# Connectors_Wires.net
KiCad netlist of a schematic drawn in Altium Designer
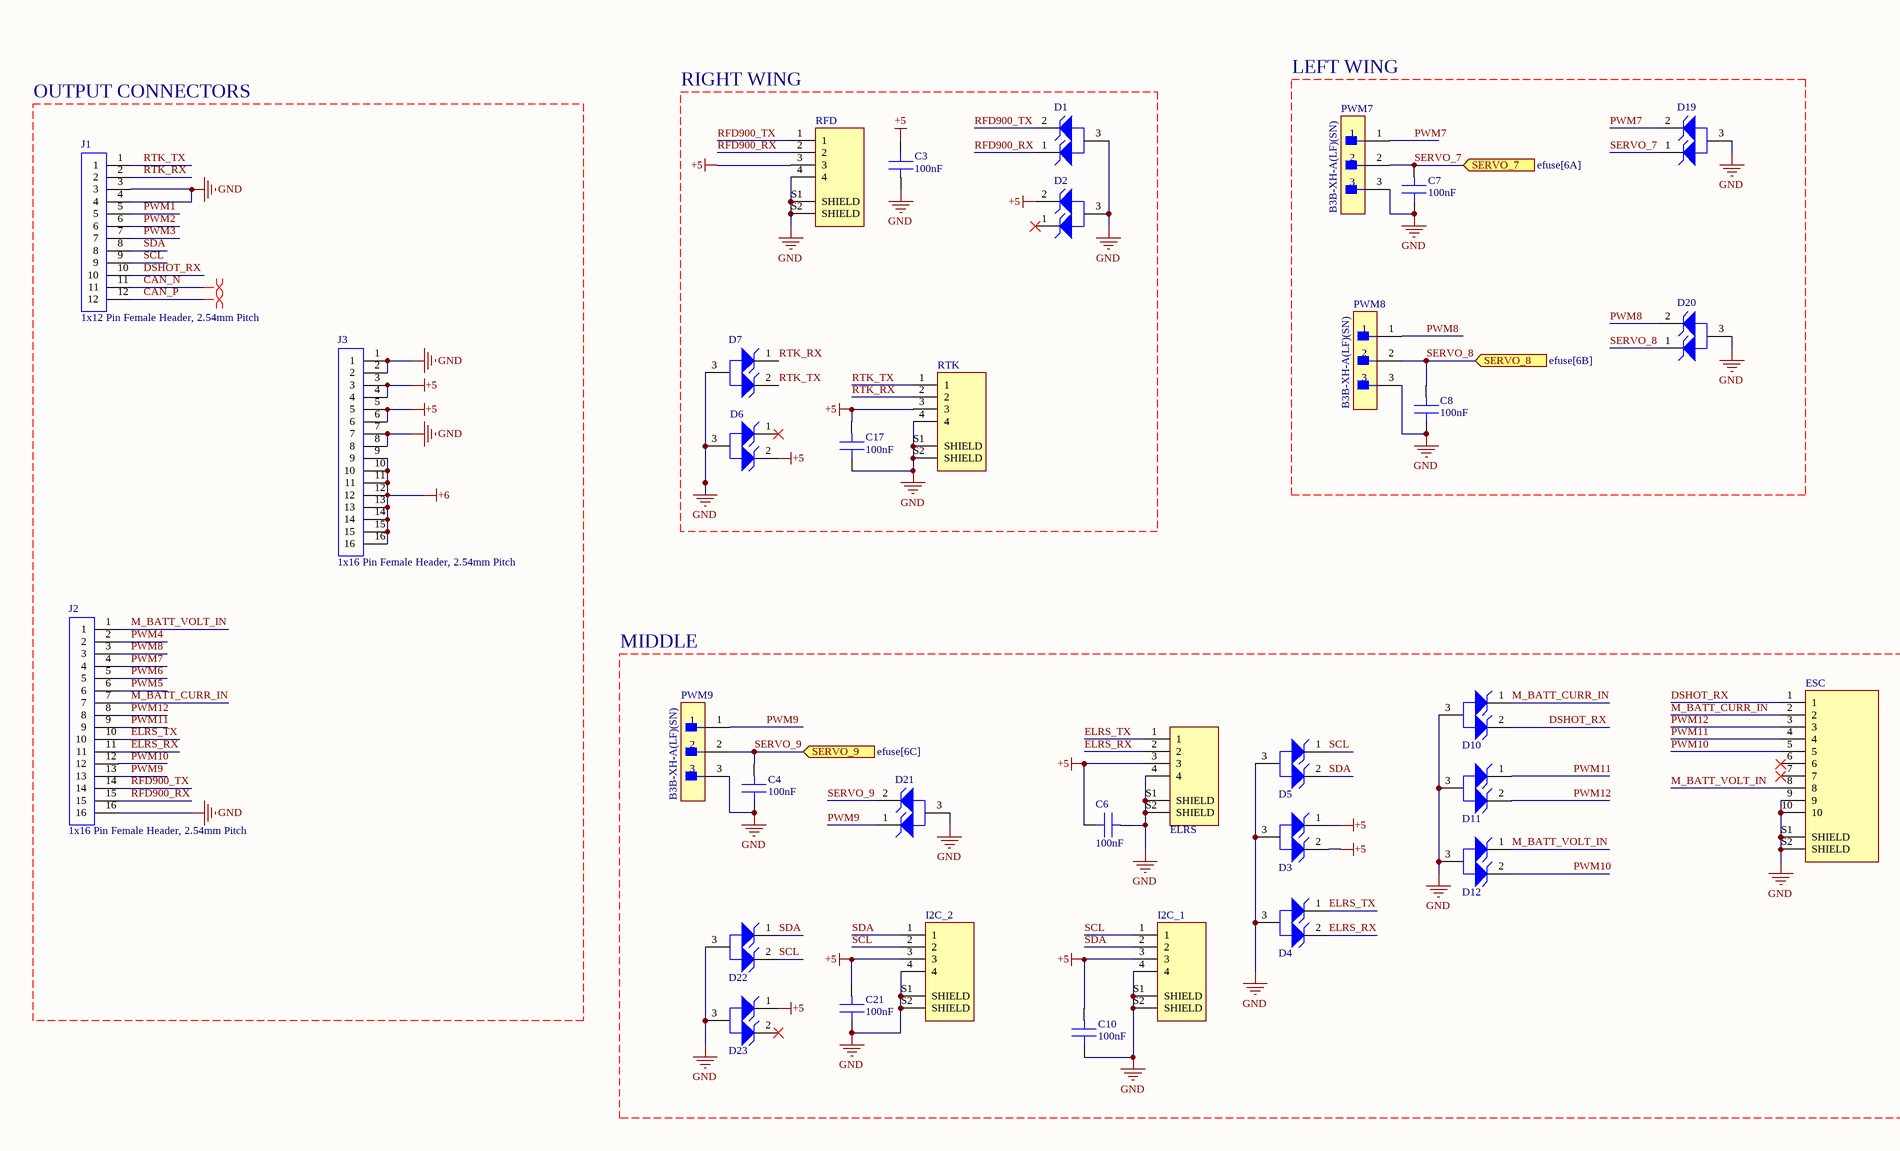
[diagram p0: Connectors_Wires.SchDoc, left]
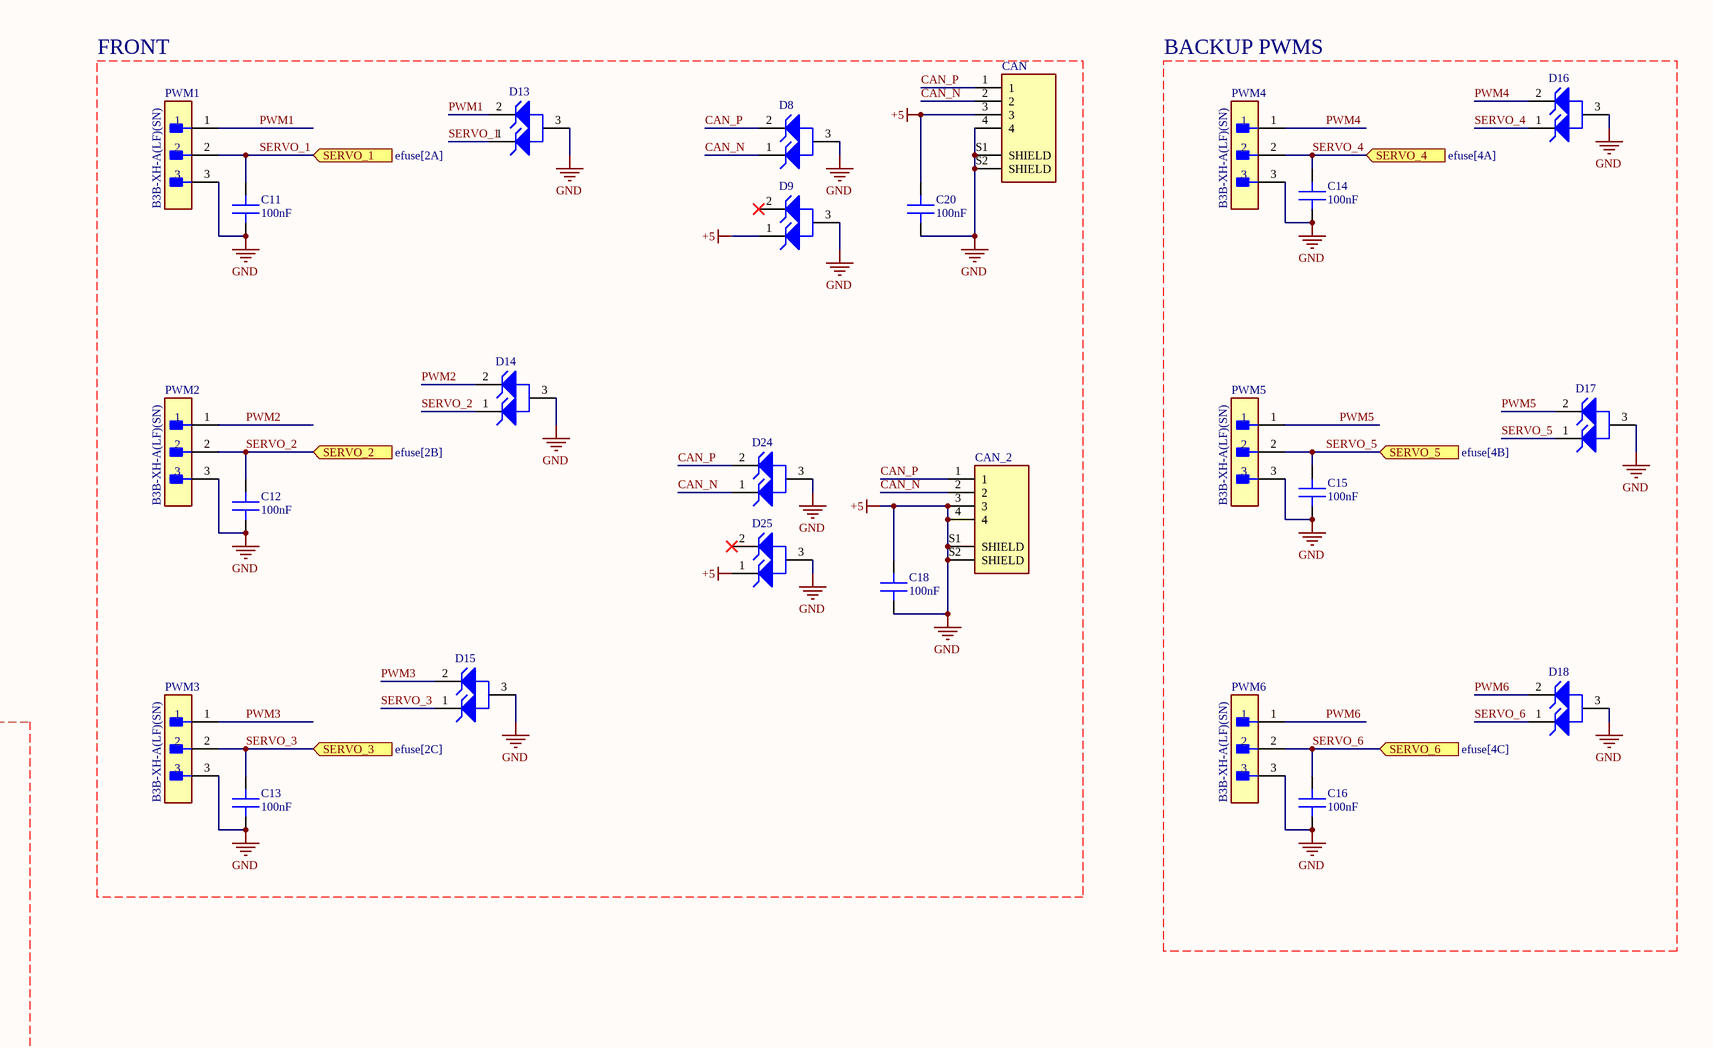
[diagram p1: Connectors_Wires.SchDoc, right]

(export (version "E")
  (design (tool "Eeschema 10.0.6"))
  (components
    (comp (ref "C3")
      (value "100nF")
      (footprint "IPC C C0402 NO SILK")
      (libsource (lib "University of British Columbia") (part "Generic CAP 1210"))
    )
    (comp (ref "C4")
      (value "100nF")
      (footprint "IPC C C0402 NO SILK")
      (libsource (lib "University of British Columbia") (part "Generic CAP 1210"))
    )
    (comp (ref "C6")
      (value "100nF")
      (footprint "IPC C C0402 NO SILK")
      (libsource (lib "University of British Columbia") (part "Generic CAP 1210"))
    )
    (comp (ref "C7")
      (value "100nF")
      (footprint "IPC C C0402 NO SILK")
      (libsource (lib "University of British Columbia") (part "Generic CAP 1210"))
    )
    (comp (ref "C8")
      (value "100nF")
      (footprint "IPC C C0402 NO SILK")
      (libsource (lib "University of British Columbia") (part "Generic CAP 1210"))
    )
    (comp (ref "C10")
      (value "100nF")
      (footprint "IPC C C0402 NO SILK")
      (libsource (lib "University of British Columbia") (part "Generic CAP 1210"))
    )
    (comp (ref "C11")
      (value "100nF")
      (footprint "IPC C C0402 NO SILK")
      (libsource (lib "University of British Columbia") (part "Generic CAP 1210"))
    )
    (comp (ref "C12")
      (value "100nF")
      (footprint "IPC C C0402 NO SILK")
      (libsource (lib "University of British Columbia") (part "Generic CAP 1210"))
    )
    (comp (ref "C13")
      (value "100nF")
      (footprint "IPC C C0402 NO SILK")
      (libsource (lib "University of British Columbia") (part "Generic CAP 1210"))
    )
    (comp (ref "C14")
      (value "100nF")
      (footprint "IPC C C0402 NO SILK")
      (libsource (lib "University of British Columbia") (part "Generic CAP 1210"))
    )
    (comp (ref "C15")
      (value "100nF")
      (footprint "IPC C C0402 NO SILK")
      (libsource (lib "University of British Columbia") (part "Generic CAP 1210"))
    )
    (comp (ref "C16")
      (value "100nF")
      (footprint "IPC C C0402 NO SILK")
      (libsource (lib "University of British Columbia") (part "Generic CAP 1210"))
    )
    (comp (ref "C17")
      (value "100nF")
      (footprint "IPC C C0402 NO SILK")
      (libsource (lib "University of British Columbia") (part "Generic CAP 1210"))
    )
    (comp (ref "C18")
      (value "100nF")
      (footprint "IPC C C0402 NO SILK")
      (libsource (lib "University of British Columbia") (part "Generic CAP 1210"))
    )
    (comp (ref "C20")
      (value "100nF")
      (footprint "IPC C C0402 NO SILK")
      (libsource (lib "University of British Columbia") (part "Generic CAP 1210"))
    )
    (comp (ref "C21")
      (value "100nF")
      (footprint "IPC C C0402 NO SILK")
      (libsource (lib "University of British Columbia") (part "Generic CAP 1210"))
    )
    (comp (ref "CAN")
      (value "BM04B-GHS-TBT(LF)(SN)(N)")
      (footprint "JST_BM04B-GHS-TBT(LF)(SN)(N)")
      (description "Conn Shrouded Header HDR 4 POS 1.25mm Solder ST Top Entry SMD T/R")
      (fields (field (name "MF") "JST") (field (name "MP") "BM04B-GHS-TBT (LF)(SN)(N)"))
      (libsource (lib "University of British Columbia") (part "BM04B-GHS-TBT(LF)(SN)(N)"))
    )
    (comp (ref "CAN_2")
      (value "BM04B-GHS-TBT(LF)(SN)(N)")
      (footprint "JST_BM04B-GHS-TBT(LF)(SN)(N)")
      (description "Conn Shrouded Header HDR 4 POS 1.25mm Solder ST Top Entry SMD T/R")
      (fields (field (name "MF") "JST") (field (name "MP") "BM04B-GHS-TBT (LF)(SN)(N)"))
      (libsource (lib "University of British Columbia") (part "BM04B-GHS-TBT(LF)(SN)(N)"))
    )
    (comp (ref "D1")
      (value "MMBZ9V1ALT1G")
      (footprint "ONSC-SOT-23-3-318-08_V")
      (fields (field (name "MANUFACTURER") "On Semiconductor"))
      (libsource (lib "Altium Content Vault") (part "ONSC-K1K2A3-3"))
    )
    (comp (ref "D2")
      (value "MMBZ9V1ALT1G")
      (footprint "ONSC-SOT-23-3-318-08_V")
      (fields (field (name "MANUFACTURER") "On Semiconductor"))
      (libsource (lib "Altium Content Vault") (part "ONSC-K1K2A3-3"))
    )
    (comp (ref "D3")
      (value "MMBZ9V1ALT1G")
      (footprint "ONSC-SOT-23-3-318-08_V")
      (fields (field (name "MANUFACTURER") "On Semiconductor"))
      (libsource (lib "Altium Content Vault") (part "ONSC-K1K2A3-3"))
    )
    (comp (ref "D4")
      (value "MMBZ9V1ALT1G")
      (footprint "ONSC-SOT-23-3-318-08_V")
      (fields (field (name "MANUFACTURER") "On Semiconductor"))
      (libsource (lib "Altium Content Vault") (part "ONSC-K1K2A3-3"))
    )
    (comp (ref "D5")
      (value "MMBZ9V1ALT1G")
      (footprint "ONSC-SOT-23-3-318-08_V")
      (fields (field (name "MANUFACTURER") "On Semiconductor"))
      (libsource (lib "Altium Content Vault") (part "ONSC-K1K2A3-3"))
    )
    (comp (ref "D6")
      (value "MMBZ9V1ALT1G")
      (footprint "ONSC-SOT-23-3-318-08_V")
      (fields (field (name "MANUFACTURER") "On Semiconductor"))
      (libsource (lib "Altium Content Vault") (part "ONSC-K1K2A3-3"))
    )
    (comp (ref "D7")
      (value "MMBZ9V1ALT1G")
      (footprint "ONSC-SOT-23-3-318-08_V")
      (fields (field (name "MANUFACTURER") "On Semiconductor"))
      (libsource (lib "Altium Content Vault") (part "ONSC-K1K2A3-3"))
    )
    (comp (ref "D8")
      (value "MMBZ9V1ALT1G")
      (footprint "ONSC-SOT-23-3-318-08_V")
      (fields (field (name "MANUFACTURER") "On Semiconductor"))
      (libsource (lib "Altium Content Vault") (part "ONSC-K1K2A3-3"))
    )
    (comp (ref "D9")
      (value "MMBZ9V1ALT1G")
      (footprint "ONSC-SOT-23-3-318-08_V")
      (fields (field (name "MANUFACTURER") "On Semiconductor"))
      (libsource (lib "Altium Content Vault") (part "ONSC-K1K2A3-3"))
    )
    (comp (ref "D10")
      (value "MMBZ9V1ALT1G")
      (footprint "ONSC-SOT-23-3-318-08_V")
      (fields (field (name "MANUFACTURER") "On Semiconductor"))
      (libsource (lib "Altium Content Vault") (part "ONSC-K1K2A3-3"))
    )
    (comp (ref "D11")
      (value "MMBZ9V1ALT1G")
      (footprint "ONSC-SOT-23-3-318-08_V")
      (fields (field (name "MANUFACTURER") "On Semiconductor"))
      (libsource (lib "Altium Content Vault") (part "ONSC-K1K2A3-3"))
    )
    (comp (ref "D12")
      (value "MMBZ9V1ALT1G")
      (footprint "ONSC-SOT-23-3-318-08_V")
      (fields (field (name "MANUFACTURER") "On Semiconductor"))
      (libsource (lib "Altium Content Vault") (part "ONSC-K1K2A3-3"))
    )
    (comp (ref "D13")
      (value "MMBZ9V1ALT1G")
      (footprint "ONSC-SOT-23-3-318-08_V")
      (fields (field (name "MANUFACTURER") "On Semiconductor"))
      (libsource (lib "Altium Content Vault") (part "ONSC-K1K2A3-3"))
    )
    (comp (ref "D14")
      (value "MMBZ9V1ALT1G")
      (footprint "ONSC-SOT-23-3-318-08_V")
      (fields (field (name "MANUFACTURER") "On Semiconductor"))
      (libsource (lib "Altium Content Vault") (part "ONSC-K1K2A3-3"))
    )
    (comp (ref "D15")
      (value "MMBZ9V1ALT1G")
      (footprint "ONSC-SOT-23-3-318-08_V")
      (fields (field (name "MANUFACTURER") "On Semiconductor"))
      (libsource (lib "Altium Content Vault") (part "ONSC-K1K2A3-3"))
    )
    (comp (ref "D16")
      (value "MMBZ9V1ALT1G")
      (footprint "ONSC-SOT-23-3-318-08_V")
      (fields (field (name "MANUFACTURER") "On Semiconductor"))
      (libsource (lib "Altium Content Vault") (part "ONSC-K1K2A3-3"))
    )
    (comp (ref "D17")
      (value "MMBZ9V1ALT1G")
      (footprint "ONSC-SOT-23-3-318-08_V")
      (fields (field (name "MANUFACTURER") "On Semiconductor"))
      (libsource (lib "Altium Content Vault") (part "ONSC-K1K2A3-3"))
    )
    (comp (ref "D18")
      (value "MMBZ9V1ALT1G")
      (footprint "ONSC-SOT-23-3-318-08_V")
      (fields (field (name "MANUFACTURER") "On Semiconductor"))
      (libsource (lib "Altium Content Vault") (part "ONSC-K1K2A3-3"))
    )
    (comp (ref "D19")
      (value "MMBZ9V1ALT1G")
      (footprint "ONSC-SOT-23-3-318-08_V")
      (fields (field (name "MANUFACTURER") "On Semiconductor"))
      (libsource (lib "Altium Content Vault") (part "ONSC-K1K2A3-3"))
    )
    (comp (ref "D20")
      (value "MMBZ9V1ALT1G")
      (footprint "ONSC-SOT-23-3-318-08_V")
      (fields (field (name "MANUFACTURER") "On Semiconductor"))
      (libsource (lib "Altium Content Vault") (part "ONSC-K1K2A3-3"))
    )
    (comp (ref "D21")
      (value "MMBZ9V1ALT1G")
      (footprint "ONSC-SOT-23-3-318-08_V")
      (fields (field (name "MANUFACTURER") "On Semiconductor"))
      (libsource (lib "Altium Content Vault") (part "ONSC-K1K2A3-3"))
    )
    (comp (ref "D22")
      (value "MMBZ9V1ALT1G")
      (footprint "ONSC-SOT-23-3-318-08_V")
      (fields (field (name "MANUFACTURER") "On Semiconductor"))
      (libsource (lib "Altium Content Vault") (part "ONSC-K1K2A3-3"))
    )
    (comp (ref "D23")
      (value "MMBZ9V1ALT1G")
      (footprint "ONSC-SOT-23-3-318-08_V")
      (fields (field (name "MANUFACTURER") "On Semiconductor"))
      (libsource (lib "Altium Content Vault") (part "ONSC-K1K2A3-3"))
    )
    (comp (ref "D24")
      (value "MMBZ9V1ALT1G")
      (footprint "ONSC-SOT-23-3-318-08_V")
      (fields (field (name "MANUFACTURER") "On Semiconductor"))
      (libsource (lib "Altium Content Vault") (part "ONSC-K1K2A3-3"))
    )
    (comp (ref "D25")
      (value "MMBZ9V1ALT1G")
      (footprint "ONSC-SOT-23-3-318-08_V")
      (fields (field (name "MANUFACTURER") "On Semiconductor"))
      (libsource (lib "Altium Content Vault") (part "ONSC-K1K2A3-3"))
    )
    (comp (ref "ELRS")
      (value "BM04B-GHS-TBT(LF)(SN)(N)")
      (footprint "JST_BM04B-GHS-TBT(LF)(SN)(N)")
      (description "Conn Shrouded Header HDR 4 POS 1.25mm Solder ST Top Entry SMD T/R")
      (fields (field (name "MF") "JST") (field (name "MP") "BM04B-GHS-TBT (LF)(SN)(N)"))
      (libsource (lib "University of British Columbia") (part "BM04B-GHS-TBT(LF)(SN)(N)"))
    )
    (comp (ref "ESC")
      (value "BM10B-GHS-TBT(LF)(SN)(N)")
      (footprint "JST_BM10B-GHS-TBT(LF)(SN)(N)")
      (description "Connector Header Surface Mount 10 position 0.049 (1.25mm)")
      (fields (field (name "MF") "JST Sales"))
      (libsource (lib "University of British Columbia") (part "BM10B-GHS-TBT(LF)(SN)(N)"))
    )
    (comp (ref "I2C_1")
      (value "BM04B-GHS-TBT(LF)(SN)(N)")
      (footprint "JST_BM04B-GHS-TBT(LF)(SN)(N)")
      (description "Conn Shrouded Header HDR 4 POS 1.25mm Solder ST Top Entry SMD T/R")
      (fields (field (name "MF") "JST") (field (name "MP") "BM04B-GHS-TBT (LF)(SN)(N)"))
      (libsource (lib "University of British Columbia") (part "BM04B-GHS-TBT(LF)(SN)(N)"))
    )
    (comp (ref "I2C_2")
      (value "BM04B-GHS-TBT(LF)(SN)(N)")
      (footprint "JST_BM04B-GHS-TBT(LF)(SN)(N)")
      (description "Conn Shrouded Header HDR 4 POS 1.25mm Solder ST Top Entry SMD T/R")
      (fields (field (name "MF") "JST") (field (name "MP") "BM04B-GHS-TBT (LF)(SN)(N)"))
      (libsource (lib "University of British Columbia") (part "BM04B-GHS-TBT(LF)(SN)(N)"))
    )
    (comp (ref "J1")
      (value "1x12 Pin Female Header, 2.54mm Pitch")
      (footprint "1x12 Pin Female Header, 2.54mm Pitch-Footprint-1")
      (libsource (lib "University of British Columbia") (part "1x12 Pin Female Header, 2.54mm Pitch-Symbol-1"))
    )
    (comp (ref "J2")
      (value "1x16 Pin Female Header, 2.54mm Pitch")
      (footprint "New footprint 1")
      (libsource (lib "University of British Columbia") (part "New symbol 1"))
    )
    (comp (ref "J3")
      (value "1x16 Pin Female Header, 2.54mm Pitch")
      (footprint "New footprint 1")
      (libsource (lib "University of British Columbia") (part "New symbol 1"))
    )
    (comp (ref "PWM1")
      (value "B3B-XH-A(LF)(SN)")
      (footprint "FP-B3B-XH-A_LF_SN-MFG")
      (description "CONN HEADER VERT 3POS 2.5MM")
      (libsource (lib "Altium Content Vault") (part "0d3f023dd272f625e17a2be33dea85f"))
    )
    (comp (ref "PWM2")
      (value "B3B-XH-A(LF)(SN)")
      (footprint "FP-B3B-XH-A_LF_SN-MFG")
      (description "CONN HEADER VERT 3POS 2.5MM")
      (libsource (lib "Altium Content Vault") (part "0d3f023dd272f625e17a2be33dea85f"))
    )
    (comp (ref "PWM3")
      (value "B3B-XH-A(LF)(SN)")
      (footprint "FP-B3B-XH-A_LF_SN-MFG")
      (description "CONN HEADER VERT 3POS 2.5MM")
      (libsource (lib "Altium Content Vault") (part "0d3f023dd272f625e17a2be33dea85f"))
    )
    (comp (ref "PWM4")
      (value "B3B-XH-A(LF)(SN)")
      (footprint "FP-B3B-XH-A_LF_SN-MFG")
      (description "CONN HEADER VERT 3POS 2.5MM")
      (libsource (lib "Altium Content Vault") (part "0d3f023dd272f625e17a2be33dea85f"))
    )
    (comp (ref "PWM5")
      (value "B3B-XH-A(LF)(SN)")
      (footprint "FP-B3B-XH-A_LF_SN-MFG")
      (description "CONN HEADER VERT 3POS 2.5MM")
      (libsource (lib "Altium Content Vault") (part "0d3f023dd272f625e17a2be33dea85f"))
    )
    (comp (ref "PWM6")
      (value "B3B-XH-A(LF)(SN)")
      (footprint "FP-B3B-XH-A_LF_SN-MFG")
      (description "CONN HEADER VERT 3POS 2.5MM")
      (libsource (lib "Altium Content Vault") (part "0d3f023dd272f625e17a2be33dea85f"))
    )
    (comp (ref "PWM7")
      (value "B3B-XH-A(LF)(SN)")
      (footprint "FP-B3B-XH-A_LF_SN-MFG")
      (description "CONN HEADER VERT 3POS 2.5MM")
      (libsource (lib "Altium Content Vault") (part "0d3f023dd272f625e17a2be33dea85f"))
    )
    (comp (ref "PWM8")
      (value "B3B-XH-A(LF)(SN)")
      (footprint "FP-B3B-XH-A_LF_SN-MFG")
      (description "CONN HEADER VERT 3POS 2.5MM")
      (libsource (lib "Altium Content Vault") (part "0d3f023dd272f625e17a2be33dea85f"))
    )
    (comp (ref "PWM9")
      (value "B3B-XH-A(LF)(SN)")
      (footprint "FP-B3B-XH-A_LF_SN-MFG")
      (description "CONN HEADER VERT 3POS 2.5MM")
      (libsource (lib "Altium Content Vault") (part "0d3f023dd272f625e17a2be33dea85f"))
    )
    (comp (ref "RFD")
      (value "BM04B-GHS-TBT(LF)(SN)(N)")
      (footprint "JST_BM04B-GHS-TBT(LF)(SN)(N)")
      (description "Conn Shrouded Header HDR 4 POS 1.25mm Solder ST Top Entry SMD T/R")
      (fields (field (name "MF") "JST") (field (name "MP") "BM04B-GHS-TBT (LF)(SN)(N)"))
      (libsource (lib "University of British Columbia") (part "BM04B-GHS-TBT(LF)(SN)(N)"))
    )
    (comp (ref "RTK")
      (value "BM04B-GHS-TBT(LF)(SN)(N)")
      (footprint "JST_BM04B-GHS-TBT(LF)(SN)(N)")
      (description "Conn Shrouded Header HDR 4 POS 1.25mm Solder ST Top Entry SMD T/R")
      (fields (field (name "MF") "JST") (field (name "MP") "BM04B-GHS-TBT (LF)(SN)(N)"))
      (libsource (lib "University of British Columbia") (part "BM04B-GHS-TBT(LF)(SN)(N)"))
    )
  )
  (nets
    (net (code "1") (name "+5") (class "Default")
      (node (ref "C10") (pin "1") (pinfunction "1_1") (pintype "passive"))
      (node (ref "C10") (pin "2") (pinfunction "2_2") (pintype "passive"))
      (node (ref "C11") (pin "2") (pinfunction "2_2") (pintype "passive"))
      (node (ref "C12") (pin "2") (pinfunction "2_2") (pintype "passive"))
      (node (ref "C13") (pin "2") (pinfunction "2_2") (pintype "passive"))
      (node (ref "C14") (pin "2") (pinfunction "2_2") (pintype "passive"))
      (node (ref "C15") (pin "2") (pinfunction "2_2") (pintype "passive"))
      (node (ref "C16") (pin "2") (pinfunction "2_2") (pintype "passive"))
      (node (ref "C17") (pin "1") (pinfunction "1_1") (pintype "passive"))
      (node (ref "C17") (pin "2") (pinfunction "2_2") (pintype "passive"))
      (node (ref "C18") (pin "1") (pinfunction "1_1") (pintype "passive"))
      (node (ref "C18") (pin "2") (pinfunction "2_2") (pintype "passive"))
      (node (ref "C20") (pin "1") (pinfunction "1_1") (pintype "passive"))
      (node (ref "C20") (pin "2") (pinfunction "2_2") (pintype "passive"))
      (node (ref "C21") (pin "1") (pinfunction "1_1") (pintype "passive"))
      (node (ref "C21") (pin "2") (pinfunction "2_2") (pintype "passive"))
      (node (ref "C3") (pin "1") (pinfunction "1_1") (pintype "passive"))
      (node (ref "C3") (pin "2") (pinfunction "2_2") (pintype "passive"))
      (node (ref "C4") (pin "2") (pinfunction "2_2") (pintype "passive"))
      (node (ref "C6") (pin "1") (pinfunction "1_1") (pintype "passive"))
      (node (ref "C6") (pin "2") (pinfunction "2_2") (pintype "passive"))
      (node (ref "C7") (pin "2") (pinfunction "2_2") (pintype "passive"))
      (node (ref "C8") (pin "2") (pinfunction "2_2") (pintype "passive"))
      (node (ref "CAN") (pin "3") (pinfunction "3_3") (pintype "passive"))
      (node (ref "CAN") (pin "4") (pinfunction "4_4") (pintype "passive"))
      (node (ref "CAN") (pin "S1") (pinfunction "SHIELD_S1") (pintype "passive"))
      (node (ref "CAN") (pin "S2") (pinfunction "SHIELD_S2") (pintype "passive"))
      (node (ref "CAN_2") (pin "3") (pinfunction "3_3") (pintype "passive"))
      (node (ref "CAN_2") (pin "4") (pinfunction "4_4") (pintype "passive"))
      (node (ref "CAN_2") (pin "S1") (pinfunction "SHIELD_S1") (pintype "passive"))
      (node (ref "CAN_2") (pin "S2") (pinfunction "SHIELD_S2") (pintype "passive"))
      (node (ref "D1") (pin "3") (pinfunction "A_3") (pintype "passive"))
      (node (ref "D10") (pin "3") (pinfunction "A_3") (pintype "passive"))
      (node (ref "D11") (pin "3") (pinfunction "A_3") (pintype "passive"))
      (node (ref "D12") (pin "3") (pinfunction "A_3") (pintype "passive"))
      (node (ref "D13") (pin "3") (pinfunction "A_3") (pintype "passive"))
      (node (ref "D14") (pin "3") (pinfunction "A_3") (pintype "passive"))
      (node (ref "D15") (pin "3") (pinfunction "A_3") (pintype "passive"))
      (node (ref "D16") (pin "3") (pinfunction "A_3") (pintype "passive"))
      (node (ref "D17") (pin "3") (pinfunction "A_3") (pintype "passive"))
      (node (ref "D18") (pin "3") (pinfunction "A_3") (pintype "passive"))
      (node (ref "D19") (pin "3") (pinfunction "A_3") (pintype "passive"))
      (node (ref "D2") (pin "2") (pinfunction "K2_2") (pintype "passive"))
      (node (ref "D2") (pin "3") (pinfunction "A_3") (pintype "passive"))
      (node (ref "D20") (pin "3") (pinfunction "A_3") (pintype "passive"))
      (node (ref "D21") (pin "3") (pinfunction "A_3") (pintype "passive"))
      (node (ref "D22") (pin "3") (pinfunction "A_3") (pintype "passive"))
      (node (ref "D23") (pin "1") (pinfunction "K1_1") (pintype "passive"))
      (node (ref "D23") (pin "3") (pinfunction "A_3") (pintype "passive"))
      (node (ref "D24") (pin "3") (pinfunction "A_3") (pintype "passive"))
      (node (ref "D25") (pin "1") (pinfunction "K1_1") (pintype "passive"))
      (node (ref "D25") (pin "3") (pinfunction "A_3") (pintype "passive"))
      (node (ref "D3") (pin "1") (pinfunction "K1_1") (pintype "passive"))
      (node (ref "D3") (pin "2") (pinfunction "K2_2") (pintype "passive"))
      (node (ref "D3") (pin "3") (pinfunction "A_3") (pintype "passive"))
      (node (ref "D4") (pin "3") (pinfunction "A_3") (pintype "passive"))
      (node (ref "D5") (pin "3") (pinfunction "A_3") (pintype "passive"))
      (node (ref "D6") (pin "2") (pinfunction "K2_2") (pintype "passive"))
      (node (ref "D6") (pin "3") (pinfunction "A_3") (pintype "passive"))
      (node (ref "D7") (pin "3") (pinfunction "A_3") (pintype "passive"))
      (node (ref "D8") (pin "3") (pinfunction "A_3") (pintype "passive"))
      (node (ref "D9") (pin "1") (pinfunction "K1_1") (pintype "passive"))
      (node (ref "D9") (pin "3") (pinfunction "A_3") (pintype "passive"))
      (node (ref "ELRS") (pin "3") (pinfunction "3_3") (pintype "passive"))
      (node (ref "ELRS") (pin "4") (pinfunction "4_4") (pintype "passive"))
      (node (ref "ELRS") (pin "S1") (pinfunction "SHIELD_S1") (pintype "passive"))
      (node (ref "ELRS") (pin "S2") (pinfunction "SHIELD_S2") (pintype "passive"))
      (node (ref "ESC") (pin "10") (pinfunction "10_10") (pintype "passive"))
      (node (ref "ESC") (pin "9") (pinfunction "9_9") (pintype "passive"))
      (node (ref "ESC") (pin "S1") (pinfunction "SHIELD_S1") (pintype "passive"))
      (node (ref "ESC") (pin "S2") (pinfunction "SHIELD_S2") (pintype "passive"))
      (node (ref "I2C_1") (pin "3") (pinfunction "3_3") (pintype "passive"))
      (node (ref "I2C_1") (pin "4") (pinfunction "4_4") (pintype "passive"))
      (node (ref "I2C_1") (pin "S1") (pinfunction "SHIELD_S1") (pintype "passive"))
      (node (ref "I2C_1") (pin "S2") (pinfunction "SHIELD_S2") (pintype "passive"))
      (node (ref "I2C_2") (pin "3") (pinfunction "3_3") (pintype "passive"))
      (node (ref "I2C_2") (pin "4") (pinfunction "4_4") (pintype "passive"))
      (node (ref "I2C_2") (pin "S1") (pinfunction "SHIELD_S1") (pintype "passive"))
      (node (ref "I2C_2") (pin "S2") (pinfunction "SHIELD_S2") (pintype "passive"))
      (node (ref "J1") (pin "3") (pinfunction "3_3") (pintype "passive"))
      (node (ref "J1") (pin "4") (pinfunction "4_4") (pintype "passive"))
      (node (ref "J2") (pin "16") (pinfunction "16_16") (pintype "passive"))
      (node (ref "J3") (pin "1") (pinfunction "1_1") (pintype "passive"))
      (node (ref "J3") (pin "2") (pinfunction "2_2") (pintype "passive"))
      (node (ref "J3") (pin "3") (pinfunction "3_3") (pintype "passive"))
      (node (ref "J3") (pin "4") (pinfunction "4_4") (pintype "passive"))
      (node (ref "J3") (pin "5") (pinfunction "5_5") (pintype "passive"))
      (node (ref "J3") (pin "6") (pinfunction "6_6") (pintype "passive"))
      (node (ref "J3") (pin "7") (pinfunction "7_7") (pintype "passive"))
      (node (ref "J3") (pin "8") (pinfunction "8_8") (pintype "passive"))
      (node (ref "PWM1") (pin "3") (pinfunction "3_3") (pintype "passive"))
      (node (ref "PWM2") (pin "3") (pinfunction "3_3") (pintype "passive"))
      (node (ref "PWM3") (pin "3") (pinfunction "3_3") (pintype "passive"))
      (node (ref "PWM4") (pin "3") (pinfunction "3_3") (pintype "passive"))
      (node (ref "PWM5") (pin "3") (pinfunction "3_3") (pintype "passive"))
      (node (ref "PWM6") (pin "3") (pinfunction "3_3") (pintype "passive"))
      (node (ref "PWM7") (pin "3") (pinfunction "3_3") (pintype "passive"))
      (node (ref "PWM8") (pin "3") (pinfunction "3_3") (pintype "passive"))
      (node (ref "PWM9") (pin "3") (pinfunction "3_3") (pintype "passive"))
      (node (ref "RFD") (pin "3") (pinfunction "3_3") (pintype "passive"))
      (node (ref "RFD") (pin "4") (pinfunction "4_4") (pintype "passive"))
      (node (ref "RFD") (pin "S1") (pinfunction "SHIELD_S1") (pintype "passive"))
      (node (ref "RFD") (pin "S2") (pinfunction "SHIELD_S2") (pintype "passive"))
      (node (ref "RTK") (pin "3") (pinfunction "3_3") (pintype "passive"))
      (node (ref "RTK") (pin "4") (pinfunction "4_4") (pintype "passive"))
      (node (ref "RTK") (pin "S1") (pinfunction "SHIELD_S1") (pintype "passive"))
      (node (ref "RTK") (pin "S2") (pinfunction "SHIELD_S2") (pintype "passive"))
    )
    (net (code "2") (name "+6") (class "Default")
      (node (ref "J3") (pin "10") (pinfunction "10_10") (pintype "passive"))
      (node (ref "J3") (pin "11") (pinfunction "11_11") (pintype "passive"))
      (node (ref "J3") (pin "12") (pinfunction "12_12") (pintype "passive"))
      (node (ref "J3") (pin "13") (pinfunction "13_13") (pintype "passive"))
      (node (ref "J3") (pin "14") (pinfunction "14_14") (pintype "passive"))
      (node (ref "J3") (pin "15") (pinfunction "15_15") (pintype "passive"))
      (node (ref "J3") (pin "16") (pinfunction "16_16") (pintype "passive"))
      (node (ref "J3") (pin "9") (pinfunction "9_9") (pintype "passive"))
    )
    (net (code "3") (name "/CAN_N") (class "Default")
      (node (ref "CAN") (pin "2") (pinfunction "2_2") (pintype "passive"))
      (node (ref "CAN_2") (pin "2") (pinfunction "2_2") (pintype "passive"))
      (node (ref "D24") (pin "1") (pinfunction "K1_1") (pintype "passive"))
      (node (ref "D8") (pin "1") (pinfunction "K1_1") (pintype "passive"))
      (node (ref "J1") (pin "11") (pinfunction "11_11") (pintype "passive"))
    )
    (net (code "4") (name "/CAN_P") (class "Default")
      (node (ref "CAN") (pin "1") (pinfunction "1_1") (pintype "passive"))
      (node (ref "CAN_2") (pin "1") (pinfunction "1_1") (pintype "passive"))
      (node (ref "D24") (pin "2") (pinfunction "K2_2") (pintype "passive"))
      (node (ref "D8") (pin "2") (pinfunction "K2_2") (pintype "passive"))
      (node (ref "J1") (pin "12") (pinfunction "12_12") (pintype "passive"))
    )
    (net (code "5") (name "/DSHOT_RX") (class "Default")
      (node (ref "D10") (pin "2") (pinfunction "K2_2") (pintype "passive"))
      (node (ref "ESC") (pin "1") (pinfunction "1_1") (pintype "passive"))
      (node (ref "J1") (pin "10") (pinfunction "10_10") (pintype "passive"))
    )
    (net (code "6") (name "/ELRS_RX") (class "Default")
      (node (ref "D4") (pin "2") (pinfunction "K2_2") (pintype "passive"))
      (node (ref "ELRS") (pin "2") (pinfunction "2_2") (pintype "passive"))
      (node (ref "J2") (pin "11") (pinfunction "11_11") (pintype "passive"))
    )
    (net (code "7") (name "/ELRS_TX") (class "Default")
      (node (ref "D4") (pin "1") (pinfunction "K1_1") (pintype "passive"))
      (node (ref "ELRS") (pin "1") (pinfunction "1_1") (pintype "passive"))
      (node (ref "J2") (pin "10") (pinfunction "10_10") (pintype "passive"))
    )
    (net (code "8") (name "/M_BATT_CURR_IN") (class "Default")
      (node (ref "D10") (pin "1") (pinfunction "K1_1") (pintype "passive"))
      (node (ref "ESC") (pin "2") (pinfunction "2_2") (pintype "passive"))
      (node (ref "J2") (pin "7") (pinfunction "7_7") (pintype "passive"))
    )
    (net (code "9") (name "/M_BATT_VOLT_IN") (class "Default")
      (node (ref "D12") (pin "1") (pinfunction "K1_1") (pintype "passive"))
      (node (ref "ESC") (pin "8") (pinfunction "8_8") (pintype "passive"))
      (node (ref "J2") (pin "1") (pinfunction "1_1") (pintype "passive"))
    )
    (net (code "10") (name "/PWM1") (class "Default")
      (node (ref "D13") (pin "2") (pinfunction "K2_2") (pintype "passive"))
      (node (ref "J1") (pin "5") (pinfunction "5_5") (pintype "passive"))
      (node (ref "PWM1") (pin "1") (pinfunction "1_1") (pintype "passive"))
    )
    (net (code "11") (name "/PWM2") (class "Default")
      (node (ref "D14") (pin "2") (pinfunction "K2_2") (pintype "passive"))
      (node (ref "J1") (pin "6") (pinfunction "6_6") (pintype "passive"))
      (node (ref "PWM2") (pin "1") (pinfunction "1_1") (pintype "passive"))
    )
    (net (code "12") (name "/PWM3") (class "Default")
      (node (ref "D15") (pin "2") (pinfunction "K2_2") (pintype "passive"))
      (node (ref "J1") (pin "7") (pinfunction "7_7") (pintype "passive"))
      (node (ref "PWM3") (pin "1") (pinfunction "1_1") (pintype "passive"))
    )
    (net (code "13") (name "/PWM4") (class "Default")
      (node (ref "D16") (pin "2") (pinfunction "K2_2") (pintype "passive"))
      (node (ref "J2") (pin "2") (pinfunction "2_2") (pintype "passive"))
      (node (ref "PWM4") (pin "1") (pinfunction "1_1") (pintype "passive"))
    )
    (net (code "14") (name "/PWM5") (class "Default")
      (node (ref "D17") (pin "2") (pinfunction "K2_2") (pintype "passive"))
      (node (ref "J2") (pin "6") (pinfunction "6_6") (pintype "passive"))
      (node (ref "PWM5") (pin "1") (pinfunction "1_1") (pintype "passive"))
    )
    (net (code "15") (name "/PWM6") (class "Default")
      (node (ref "D18") (pin "2") (pinfunction "K2_2") (pintype "passive"))
      (node (ref "J2") (pin "5") (pinfunction "5_5") (pintype "passive"))
      (node (ref "PWM6") (pin "1") (pinfunction "1_1") (pintype "passive"))
    )
    (net (code "16") (name "/PWM7") (class "Default")
      (node (ref "D19") (pin "2") (pinfunction "K2_2") (pintype "passive"))
      (node (ref "J2") (pin "4") (pinfunction "4_4") (pintype "passive"))
      (node (ref "PWM7") (pin "1") (pinfunction "1_1") (pintype "passive"))
    )
    (net (code "17") (name "/PWM8") (class "Default")
      (node (ref "D20") (pin "2") (pinfunction "K2_2") (pintype "passive"))
      (node (ref "J2") (pin "3") (pinfunction "3_3") (pintype "passive"))
      (node (ref "PWM8") (pin "1") (pinfunction "1_1") (pintype "passive"))
    )
    (net (code "18") (name "/PWM9") (class "Default")
      (node (ref "D21") (pin "1") (pinfunction "K1_1") (pintype "passive"))
      (node (ref "J2") (pin "13") (pinfunction "13_13") (pintype "passive"))
      (node (ref "PWM9") (pin "1") (pinfunction "1_1") (pintype "passive"))
    )
    (net (code "19") (name "/PWM10") (class "Default")
      (node (ref "D12") (pin "2") (pinfunction "K2_2") (pintype "passive"))
      (node (ref "ESC") (pin "5") (pinfunction "5_5") (pintype "passive"))
      (node (ref "J2") (pin "12") (pinfunction "12_12") (pintype "passive"))
    )
    (net (code "20") (name "/PWM11") (class "Default")
      (node (ref "D11") (pin "1") (pinfunction "K1_1") (pintype "passive"))
      (node (ref "ESC") (pin "4") (pinfunction "4_4") (pintype "passive"))
      (node (ref "J2") (pin "9") (pinfunction "9_9") (pintype "passive"))
    )
    (net (code "21") (name "/PWM12") (class "Default")
      (node (ref "D11") (pin "2") (pinfunction "K2_2") (pintype "passive"))
      (node (ref "ESC") (pin "3") (pinfunction "3_3") (pintype "passive"))
      (node (ref "J2") (pin "8") (pinfunction "8_8") (pintype "passive"))
    )
    (net (code "22") (name "/RFD900_RX") (class "Default")
      (node (ref "D1") (pin "1") (pinfunction "K1_1") (pintype "passive"))
      (node (ref "J2") (pin "15") (pinfunction "15_15") (pintype "passive"))
      (node (ref "RFD") (pin "2") (pinfunction "2_2") (pintype "passive"))
    )
    (net (code "23") (name "/RFD900_TX") (class "Default")
      (node (ref "D1") (pin "2") (pinfunction "K2_2") (pintype "passive"))
      (node (ref "J2") (pin "14") (pinfunction "14_14") (pintype "passive"))
      (node (ref "RFD") (pin "1") (pinfunction "1_1") (pintype "passive"))
    )
    (net (code "24") (name "/RTK_RX") (class "Default")
      (node (ref "D7") (pin "1") (pinfunction "K1_1") (pintype "passive"))
      (node (ref "J1") (pin "2") (pinfunction "2_2") (pintype "passive"))
      (node (ref "RTK") (pin "2") (pinfunction "2_2") (pintype "passive"))
    )
    (net (code "25") (name "/RTK_TX") (class "Default")
      (node (ref "D7") (pin "2") (pinfunction "K2_2") (pintype "passive"))
      (node (ref "J1") (pin "1") (pinfunction "1_1") (pintype "passive"))
      (node (ref "RTK") (pin "1") (pinfunction "1_1") (pintype "passive"))
    )
    (net (code "26") (name "/SCL") (class "Default")
      (node (ref "D22") (pin "2") (pinfunction "K2_2") (pintype "passive"))
      (node (ref "D5") (pin "1") (pinfunction "K1_1") (pintype "passive"))
      (node (ref "I2C_1") (pin "1") (pinfunction "1_1") (pintype "passive"))
      (node (ref "I2C_2") (pin "2") (pinfunction "2_2") (pintype "passive"))
      (node (ref "J1") (pin "9") (pinfunction "9_9") (pintype "passive"))
    )
    (net (code "27") (name "/SDA") (class "Default")
      (node (ref "D22") (pin "1") (pinfunction "K1_1") (pintype "passive"))
      (node (ref "D5") (pin "2") (pinfunction "K2_2") (pintype "passive"))
      (node (ref "I2C_1") (pin "2") (pinfunction "2_2") (pintype "passive"))
      (node (ref "I2C_2") (pin "1") (pinfunction "1_1") (pintype "passive"))
      (node (ref "J1") (pin "8") (pinfunction "8_8") (pintype "passive"))
    )
    (net (code "28") (name "/SERVO_1") (class "Default")
      (node (ref "C11") (pin "1") (pinfunction "1_1") (pintype "passive"))
      (node (ref "D13") (pin "1") (pinfunction "K1_1") (pintype "passive"))
      (node (ref "PWM1") (pin "2") (pinfunction "2_2") (pintype "passive"))
    )
    (net (code "29") (name "/SERVO_2") (class "Default")
      (node (ref "C12") (pin "1") (pinfunction "1_1") (pintype "passive"))
      (node (ref "D14") (pin "1") (pinfunction "K1_1") (pintype "passive"))
      (node (ref "PWM2") (pin "2") (pinfunction "2_2") (pintype "passive"))
    )
    (net (code "30") (name "/SERVO_3") (class "Default")
      (node (ref "C13") (pin "1") (pinfunction "1_1") (pintype "passive"))
      (node (ref "D15") (pin "1") (pinfunction "K1_1") (pintype "passive"))
      (node (ref "PWM3") (pin "2") (pinfunction "2_2") (pintype "passive"))
    )
    (net (code "31") (name "/SERVO_4") (class "Default")
      (node (ref "C14") (pin "1") (pinfunction "1_1") (pintype "passive"))
      (node (ref "D16") (pin "1") (pinfunction "K1_1") (pintype "passive"))
      (node (ref "PWM4") (pin "2") (pinfunction "2_2") (pintype "passive"))
    )
    (net (code "32") (name "/SERVO_5") (class "Default")
      (node (ref "C15") (pin "1") (pinfunction "1_1") (pintype "passive"))
      (node (ref "D17") (pin "1") (pinfunction "K1_1") (pintype "passive"))
      (node (ref "PWM5") (pin "2") (pinfunction "2_2") (pintype "passive"))
    )
    (net (code "33") (name "/SERVO_6") (class "Default")
      (node (ref "C16") (pin "1") (pinfunction "1_1") (pintype "passive"))
      (node (ref "D18") (pin "1") (pinfunction "K1_1") (pintype "passive"))
      (node (ref "PWM6") (pin "2") (pinfunction "2_2") (pintype "passive"))
    )
    (net (code "34") (name "/SERVO_7") (class "Default")
      (node (ref "C7") (pin "1") (pinfunction "1_1") (pintype "passive"))
      (node (ref "D19") (pin "1") (pinfunction "K1_1") (pintype "passive"))
      (node (ref "PWM7") (pin "2") (pinfunction "2_2") (pintype "passive"))
    )
    (net (code "35") (name "/SERVO_8") (class "Default")
      (node (ref "C8") (pin "1") (pinfunction "1_1") (pintype "passive"))
      (node (ref "D20") (pin "1") (pinfunction "K1_1") (pintype "passive"))
      (node (ref "PWM8") (pin "2") (pinfunction "2_2") (pintype "passive"))
    )
    (net (code "36") (name "/SERVO_9") (class "Default")
      (node (ref "C4") (pin "1") (pinfunction "1_1") (pintype "passive"))
      (node (ref "D21") (pin "2") (pinfunction "K2_2") (pintype "passive"))
      (node (ref "PWM9") (pin "2") (pinfunction "2_2") (pintype "passive"))
    )
    (net (code "37") (name "unconnected-(D2-K1-Pad1)") (class "Default")
      (node (ref "D2") (pin "1") (pinfunction "K1_1") (pintype "passive+no_connect"))
    )
    (net (code "38") (name "unconnected-(D6-K1-Pad1)") (class "Default")
      (node (ref "D6") (pin "1") (pinfunction "K1_1") (pintype "passive+no_connect"))
    )
    (net (code "39") (name "unconnected-(D9-K2-Pad2)") (class "Default")
      (node (ref "D9") (pin "2") (pinfunction "K2_2") (pintype "passive+no_connect"))
    )
    (net (code "40") (name "unconnected-(D23-K2-Pad2)") (class "Default")
      (node (ref "D23") (pin "2") (pinfunction "K2_2") (pintype "passive+no_connect"))
    )
    (net (code "41") (name "unconnected-(D25-K2-Pad2)") (class "Default")
      (node (ref "D25") (pin "2") (pinfunction "K2_2") (pintype "passive+no_connect"))
    )
    (net (code "42") (name "unconnected-(ESC-Pad6)") (class "Default")
      (node (ref "ESC") (pin "6") (pinfunction "6_6") (pintype "passive+no_connect"))
    )
    (net (code "43") (name "unconnected-(ESC-Pad7)") (class "Default")
      (node (ref "ESC") (pin "7") (pinfunction "7_7") (pintype "passive+no_connect"))
    )
  )
)
